# Optical_Decoder_Schematic.net
KiCad netlist of a schematic drawn in Altium Designer
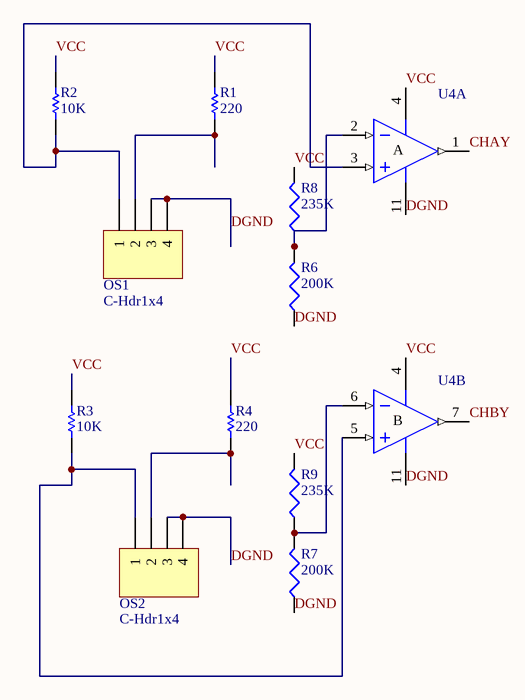
[diagram p0: Optical Decoder Schematic.SchDoc]

(export (version "E")
  (design (tool "Eeschema 10.0.6"))
  (components
    (comp (ref "OS1")
      (value "C-Hdr1x4")
      (footprint "HDR1X4_LGE1.0")
      (description "Header, 4-Pin")
      (fields (field (name "PUBLISHER") "Altium Limited"))
      (libsource (lib "PartsDatabaseV13p1") (part "C-Hdr1x4"))
    )
    (comp (ref "OS2")
      (value "C-Hdr1x4")
      (footprint "HDR1X4_LGE1.0")
      (description "Header, 4-Pin")
      (fields (field (name "PUBLISHER") "Altium Limited"))
      (libsource (lib "PartsDatabaseV13p1") (part "C-Hdr1x4"))
    )
    (comp (ref "R1")
      (value "220")
      (footprint "AXIAL-0.3")
      (description "Resistor")
      (fields (field (name "PUBLISHER") "Altium Limited"))
      (libsource (lib "Miscellaneous Devices") (part "Res1"))
    )
    (comp (ref "R2")
      (value "10K")
      (footprint "AXIAL-0.3")
      (description "Resistor")
      (fields (field (name "PUBLISHER") "Altium Limited"))
      (libsource (lib "Miscellaneous Devices") (part "Res1"))
    )
    (comp (ref "R3")
      (value "10K")
      (footprint "AXIAL-0.3")
      (description "Resistor")
      (fields (field (name "PUBLISHER") "Altium Limited"))
      (libsource (lib "Miscellaneous Devices") (part "Res1"))
    )
    (comp (ref "R4")
      (value "220")
      (footprint "AXIAL-0.3")
      (description "Resistor")
      (fields (field (name "PUBLISHER") "Altium Limited"))
      (libsource (lib "Miscellaneous Devices") (part "Res1"))
    )
    (comp (ref "R6")
      (value "200K")
      (footprint "Res10mm_LGE1.0")
      (description "resistor (specify value)")
      (fields (field (name "PUBLISHER") "Altium Limited"))
      (libsource (lib "PartsDatabaseV13p1") (part "G-Res"))
    )
    (comp (ref "R7")
      (value "200K")
      (footprint "Res10mm_LGE1.0")
      (description "resistor (specify value)")
      (fields (field (name "PUBLISHER") "Altium Limited"))
      (libsource (lib "PartsDatabaseV13p1") (part "G-Res"))
    )
    (comp (ref "R8")
      (value "235K")
      (footprint "Res10mm_LGE1.0")
      (description "resistor (specify value)")
      (fields (field (name "PUBLISHER") "Altium Limited"))
      (libsource (lib "PartsDatabaseV13p1") (part "G-Res"))
    )
    (comp (ref "R9")
      (value "235K")
      (footprint "Res10mm_LGE1.0")
      (description "resistor (specify value)")
      (fields (field (name "PUBLISHER") "Altium Limited"))
      (libsource (lib "PartsDatabaseV13p1") (part "G-Res"))
    )
    (comp (ref "U4")
      (value "O-OpAmp074")
      (footprint "DIP14_LGE1.0")
      (description "op amp (TL074)")
      (fields (field (name "PUBLISHER") "Altium Limited"))
      (libsource (lib "PartsDatabaseV13p1") (part "O-OpAmp074"))
    )
  )
  (nets
    (net (code "1") (name "/CHAY") (class "Default")
      (node (ref "U4") (pin "1") (pinfunction "OUT_1") (pintype "output"))
    )
    (net (code "2") (name "/CHBY") (class "Default")
      (node (ref "U4") (pin "7") (pinfunction "OUT_7") (pintype "output"))
    )
    (net (code "3") (name "/DGND") (class "Default")
      (node (ref "OS1") (pin "3") (pinfunction "3_3") (pintype "passive"))
      (node (ref "OS1") (pin "4") (pinfunction "4_4") (pintype "passive"))
      (node (ref "OS2") (pin "3") (pinfunction "3_3") (pintype "passive"))
      (node (ref "OS2") (pin "4") (pinfunction "4_4") (pintype "passive"))
      (node (ref "R6") (pin "1") (pinfunction "1_1") (pintype "passive"))
      (node (ref "R7") (pin "1") (pinfunction "1_1") (pintype "passive"))
      (node (ref "U4") (pin "11") (pinfunction "V-_11") (pintype "power_in"))
    )
    (net (code "4") (name "/VCC") (class "Default")
      (node (ref "R1") (pin "2") (pinfunction "2_2") (pintype "passive"))
      (node (ref "R2") (pin "2") (pinfunction "2_2") (pintype "passive"))
      (node (ref "R3") (pin "2") (pinfunction "2_2") (pintype "passive"))
      (node (ref "R4") (pin "2") (pinfunction "2_2") (pintype "passive"))
      (node (ref "R8") (pin "2") (pinfunction "2_2") (pintype "passive"))
      (node (ref "R9") (pin "2") (pinfunction "2_2") (pintype "passive"))
      (node (ref "U4") (pin "4") (pinfunction "V+_4") (pintype "power_in"))
    )
    (net (code "5") (name "Net-(OS1-Pad2)") (class "Default")
      (node (ref "OS1") (pin "2") (pinfunction "2_2") (pintype "passive"))
      (node (ref "R1") (pin "1") (pinfunction "1_1") (pintype "passive"))
    )
    (net (code "6") (name "Net-(OS2-Pad2)") (class "Default")
      (node (ref "OS2") (pin "2") (pinfunction "2_2") (pintype "passive"))
      (node (ref "R4") (pin "1") (pinfunction "1_1") (pintype "passive"))
    )
    (net (code "7") (name "Net-(U4A-IN+)") (class "Default")
      (node (ref "OS1") (pin "1") (pinfunction "1_1") (pintype "passive"))
      (node (ref "R2") (pin "1") (pinfunction "1_1") (pintype "passive"))
      (node (ref "U4") (pin "3") (pinfunction "IN+_3") (pintype "input"))
    )
    (net (code "8") (name "Net-(U4A-IN-)") (class "Default")
      (node (ref "R6") (pin "2") (pinfunction "2_2") (pintype "passive"))
      (node (ref "R8") (pin "1") (pinfunction "1_1") (pintype "passive"))
      (node (ref "U4") (pin "2") (pinfunction "IN-_2") (pintype "input"))
    )
    (net (code "9") (name "Net-(U4B-IN+)") (class "Default")
      (node (ref "OS2") (pin "1") (pinfunction "1_1") (pintype "passive"))
      (node (ref "R3") (pin "1") (pinfunction "1_1") (pintype "passive"))
      (node (ref "U4") (pin "5") (pinfunction "IN+_5") (pintype "input"))
    )
    (net (code "10") (name "Net-(U4B-IN-)") (class "Default")
      (node (ref "R7") (pin "2") (pinfunction "2_2") (pintype "passive"))
      (node (ref "R9") (pin "1") (pinfunction "1_1") (pintype "passive"))
      (node (ref "U4") (pin "6") (pinfunction "IN-_6") (pintype "input"))
    )
  )
)
